# Caffeine.net
KiCad netlist of a schematic drawn in EAGLE
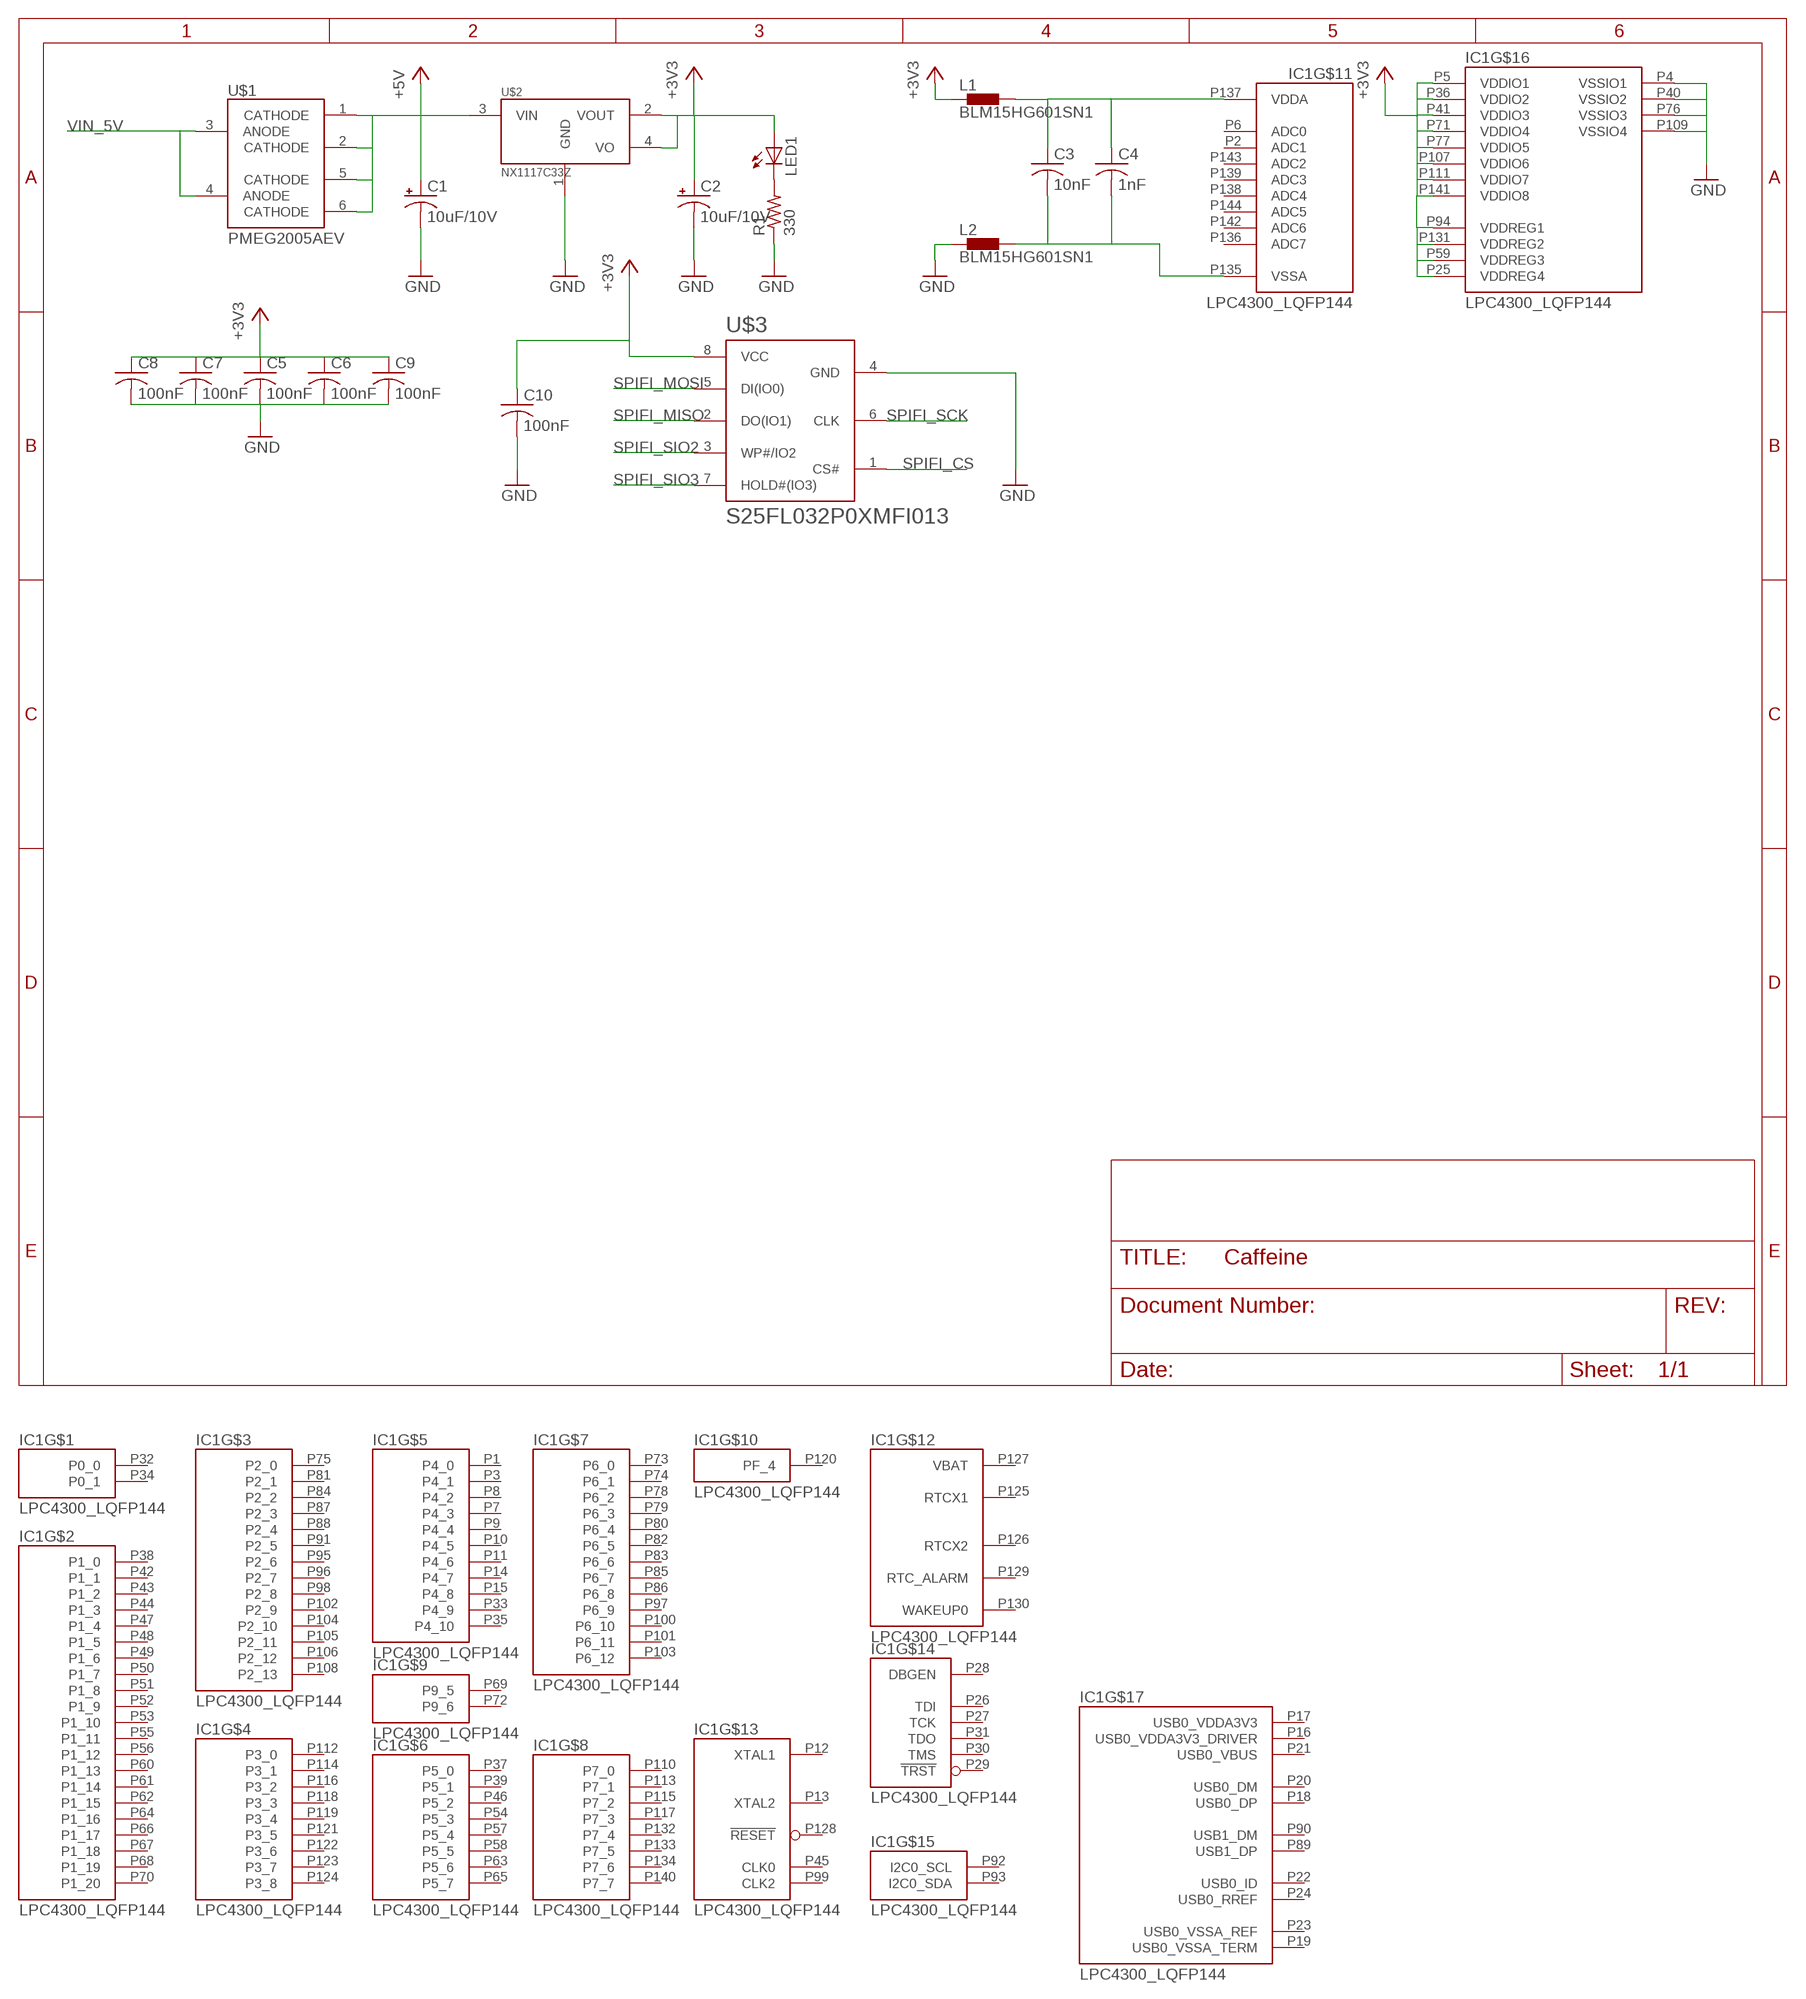
[diagram p0: schematic, sheet 1]

(export (version "E")
  (design (tool "Eeschema 10.0.6"))
  (components
    (comp (ref "C1")
      (value "10uF/10V")
      (footprint "eagle-import:CT3216")
      (libsource (lib "eagle-import") (part "CPOL-USCT3216"))
    )
    (comp (ref "C2")
      (value "10uF/10V")
      (footprint "eagle-import:CT3216")
      (libsource (lib "eagle-import") (part "CPOL-USCT3216"))
    )
    (comp (ref "C3")
      (value "10nF")
      (footprint "eagle-import:C1206")
      (libsource (lib "eagle-import") (part "C-USC1206"))
    )
    (comp (ref "C4")
      (value "1nF")
      (footprint "eagle-import:C1206")
      (libsource (lib "eagle-import") (part "C-USC1206"))
    )
    (comp (ref "C5")
      (value "100nF")
      (footprint "eagle-import:C1206")
      (libsource (lib "eagle-import") (part "C-USC1206"))
    )
    (comp (ref "C6")
      (value "100nF")
      (footprint "eagle-import:C1206")
      (libsource (lib "eagle-import") (part "C-USC1206"))
    )
    (comp (ref "C7")
      (value "100nF")
      (footprint "eagle-import:C1206")
      (libsource (lib "eagle-import") (part "C-USC1206"))
    )
    (comp (ref "C8")
      (value "100nF")
      (footprint "eagle-import:C1206")
      (libsource (lib "eagle-import") (part "C-USC1206"))
    )
    (comp (ref "C9")
      (value "100nF")
      (footprint "eagle-import:C1206")
      (libsource (lib "eagle-import") (part "C-USC1206"))
    )
    (comp (ref "C10")
      (value "100nF")
      (footprint "eagle-import:C1206")
      (libsource (lib "eagle-import") (part "C-USC1206"))
    )
    (comp (ref "IC1")
      (value "LPC4300_LQFP144")
      (footprint "eagle-import:LQFP144")
      (libsource (lib "eagle-import") (part "LPC4300_LQFP144"))
    )
    (comp (ref "L1")
      (value "BLM15HG601SN1")
      (footprint "eagle-import:0402")
      (libsource (lib "eagle-import") (part "BLM15HG601SN1"))
    )
    (comp (ref "L2")
      (value "BLM15HG601SN1")
      (footprint "eagle-import:0402")
      (libsource (lib "eagle-import") (part "BLM15HG601SN1"))
    )
    (comp (ref "LED1")
      (value "LEDCHIPLED_1206")
      (footprint "eagle-import:CHIPLED_1206")
      (libsource (lib "eagle-import") (part "LEDCHIPLED_1206"))
    )
    (comp (ref "R1")
      (value "330")
      (footprint "eagle-import:R1206")
      (libsource (lib "eagle-import") (part "R-US_R1206"))
    )
    (comp (ref "U$1")
      (value "PMEG2005AEV")
      (footprint "eagle-import:SOT666")
      (libsource (lib "eagle-import") (part "PMEG2005AEV"))
    )
    (comp (ref "U$2")
      (value "NX1117C33Z")
      (footprint "eagle-import:SOT223")
      (libsource (lib "eagle-import") (part "NX1117C33Z"))
    )
    (comp (ref "U$3")
      (value "S25FL032P0XMFI013")
      (footprint "eagle-import:SOC008")
      (libsource (lib "eagle-import") (part "S25FL032P0XMFI013"))
    )
  )
  (nets
    (net (code "1") (name "+3V3") (class "Default")
      (node (ref "C10") (pin "1") (pinfunction "1_1") (pintype "passive"))
      (node (ref "C2") (pin "+") (pinfunction "+_+") (pintype "passive"))
      (node (ref "C5") (pin "1") (pinfunction "1_1") (pintype "passive"))
      (node (ref "C6") (pin "1") (pinfunction "1_1") (pintype "passive"))
      (node (ref "C7") (pin "1") (pinfunction "1_1") (pintype "passive"))
      (node (ref "C8") (pin "1") (pinfunction "1_1") (pintype "passive"))
      (node (ref "C9") (pin "1") (pinfunction "1_1") (pintype "passive"))
      (node (ref "IC1") (pin "P107") (pinfunction "VDDIO6_P107") (pintype "power_in"))
      (node (ref "IC1") (pin "P111") (pinfunction "VDDIO7_P111") (pintype "power_in"))
      (node (ref "IC1") (pin "P131") (pinfunction "VDDREG2_P131") (pintype "power_in"))
      (node (ref "IC1") (pin "P141") (pinfunction "VDDIO8_P141") (pintype "power_in"))
      (node (ref "IC1") (pin "P25") (pinfunction "VDDREG4_P25") (pintype "power_in"))
      (node (ref "IC1") (pin "P36") (pinfunction "VDDIO2_P36") (pintype "power_in"))
      (node (ref "IC1") (pin "P41") (pinfunction "VDDIO3_P41") (pintype "power_in"))
      (node (ref "IC1") (pin "P5") (pinfunction "VDDIO1_P5") (pintype "power_in"))
      (node (ref "IC1") (pin "P59") (pinfunction "VDDREG3_P59") (pintype "power_in"))
      (node (ref "IC1") (pin "P71") (pinfunction "VDDIO4_P71") (pintype "power_in"))
      (node (ref "IC1") (pin "P77") (pinfunction "VDDIO5_P77") (pintype "power_in"))
      (node (ref "IC1") (pin "P94") (pinfunction "VDDREG1_P94") (pintype "power_in"))
      (node (ref "L1") (pin "1") (pinfunction "1_1") (pintype "passive"))
      (node (ref "LED1") (pin "A") (pinfunction "A_A") (pintype "passive"))
      (node (ref "U$2") (pin "2") (pinfunction "VOUT_2") (pintype "power_in"))
      (node (ref "U$2") (pin "4") (pinfunction "VO_4") (pintype "power_in"))
      (node (ref "U$3") (pin "8") (pinfunction "VCC_8") (pintype "power_in"))
    )
    (net (code "2") (name "+5V") (class "Default")
      (node (ref "C1") (pin "+") (pinfunction "+_+") (pintype "passive"))
      (node (ref "U$1") (pin "1") (pinfunction "CATHODE_1") (pintype "passive"))
      (node (ref "U$1") (pin "2") (pinfunction "CATHODE_2") (pintype "passive"))
      (node (ref "U$1") (pin "5") (pinfunction "CATHODE_5") (pintype "passive"))
      (node (ref "U$1") (pin "6") (pinfunction "CATHODE_6") (pintype "passive"))
      (node (ref "U$2") (pin "3") (pinfunction "VIN_3") (pintype "power_in"))
    )
    (net (code "3") (name "/SPIFI_CS") (class "Default")
      (node (ref "U$3") (pin "1") (pinfunction "CS#_1") (pintype "bidirectional"))
    )
    (net (code "4") (name "/SPIFI_MISO") (class "Default")
      (node (ref "U$3") (pin "2") (pinfunction "DO(IO1)_2") (pintype "bidirectional"))
    )
    (net (code "5") (name "/SPIFI_MOSI") (class "Default")
      (node (ref "U$3") (pin "5") (pinfunction "DI(IO0)_5") (pintype "bidirectional"))
    )
    (net (code "6") (name "/SPIFI_SCK") (class "Default")
      (node (ref "U$3") (pin "6") (pinfunction "CLK_6") (pintype "bidirectional"))
    )
    (net (code "7") (name "/SPIFI_SIO2") (class "Default")
      (node (ref "U$3") (pin "3") (pinfunction "WP#/IO2_3") (pintype "bidirectional"))
    )
    (net (code "8") (name "/SPIFI_SIO3") (class "Default")
      (node (ref "U$3") (pin "7") (pinfunction "HOLD#(IO3)_7") (pintype "bidirectional"))
    )
    (net (code "9") (name "/VBAT") (class "Default")
      (node (ref "IC1") (pin "P127") (pinfunction "VBAT_P127") (pintype "power_in"))
    )
    (net (code "10") (name "/VIN_5V") (class "Default")
      (node (ref "U$1") (pin "3") (pinfunction "ANODE_3") (pintype "passive"))
      (node (ref "U$1") (pin "4") (pinfunction "ANODE_4") (pintype "passive"))
    )
    (net (code "11") (name "GND") (class "Default")
      (node (ref "C1") (pin "-") (pinfunction "-_-") (pintype "passive"))
      (node (ref "C10") (pin "2") (pinfunction "2_2") (pintype "passive"))
      (node (ref "C2") (pin "-") (pinfunction "-_-") (pintype "passive"))
      (node (ref "C5") (pin "2") (pinfunction "2_2") (pintype "passive"))
      (node (ref "C6") (pin "2") (pinfunction "2_2") (pintype "passive"))
      (node (ref "C7") (pin "2") (pinfunction "2_2") (pintype "passive"))
      (node (ref "C8") (pin "2") (pinfunction "2_2") (pintype "passive"))
      (node (ref "C9") (pin "2") (pinfunction "2_2") (pintype "passive"))
      (node (ref "IC1") (pin "P109") (pinfunction "VSSIO4_P109") (pintype "power_in"))
      (node (ref "IC1") (pin "P4") (pinfunction "VSSIO1_P4") (pintype "power_in"))
      (node (ref "IC1") (pin "P40") (pinfunction "VSSIO2_P40") (pintype "power_in"))
      (node (ref "IC1") (pin "P76") (pinfunction "VSSIO3_P76") (pintype "power_in"))
      (node (ref "L2") (pin "1") (pinfunction "1_1") (pintype "passive"))
      (node (ref "R1") (pin "1") (pinfunction "1_1") (pintype "passive"))
      (node (ref "U$2") (pin "1") (pinfunction "GND_1") (pintype "power_in"))
      (node (ref "U$3") (pin "4") (pinfunction "GND_4") (pintype "power_in"))
    )
    (net (code "12") (name "Net-(IC1C-VDDA)") (class "Default")
      (node (ref "C3") (pin "1") (pinfunction "1_1") (pintype "passive"))
      (node (ref "C4") (pin "1") (pinfunction "1_1") (pintype "passive"))
      (node (ref "IC1") (pin "P137") (pinfunction "VDDA_P137") (pintype "power_in"))
      (node (ref "L1") (pin "2") (pinfunction "2_2") (pintype "passive"))
    )
    (net (code "13") (name "Net-(IC1C-VSSA)") (class "Default")
      (node (ref "C3") (pin "2") (pinfunction "2_2") (pintype "passive"))
      (node (ref "C4") (pin "2") (pinfunction "2_2") (pintype "passive"))
      (node (ref "IC1") (pin "P135") (pinfunction "VSSA_P135") (pintype "power_in"))
      (node (ref "L2") (pin "2") (pinfunction "2_2") (pintype "passive"))
    )
    (net (code "14") (name "Net-(LED1-PadC)") (class "Default")
      (node (ref "LED1") (pin "C") (pinfunction "C_C") (pintype "passive"))
      (node (ref "R1") (pin "2") (pinfunction "2_2") (pintype "passive"))
    )
    (net (code "15") (name "unconnected-(IC1A-P0_0-PadP32)") (class "Default")
      (node (ref "IC1") (pin "P32") (pinfunction "P0_0_P32") (pintype "bidirectional"))
    )
    (net (code "16") (name "unconnected-(IC1A-P0_1-PadP34)") (class "Default")
      (node (ref "IC1") (pin "P34") (pinfunction "P0_1_P34") (pintype "bidirectional"))
    )
    (net (code "17") (name "unconnected-(IC1B-PF_4-PadP120)") (class "Default")
      (node (ref "IC1") (pin "P120") (pinfunction "PF_4_P120") (pintype "bidirectional"))
    )
    (net (code "18") (name "unconnected-(IC1C-ADC0-PadP6)") (class "Default")
      (node (ref "IC1") (pin "P6") (pinfunction "ADC0_P6") (pintype "input"))
    )
    (net (code "19") (name "unconnected-(IC1C-ADC1-PadP2)") (class "Default")
      (node (ref "IC1") (pin "P2") (pinfunction "ADC1_P2") (pintype "input"))
    )
    (net (code "20") (name "unconnected-(IC1C-ADC2-PadP143)") (class "Default")
      (node (ref "IC1") (pin "P143") (pinfunction "ADC2_P143") (pintype "input"))
    )
    (net (code "21") (name "unconnected-(IC1C-ADC3-PadP139)") (class "Default")
      (node (ref "IC1") (pin "P139") (pinfunction "ADC3_P139") (pintype "input"))
    )
    (net (code "22") (name "unconnected-(IC1C-ADC4-PadP138)") (class "Default")
      (node (ref "IC1") (pin "P138") (pinfunction "ADC4_P138") (pintype "input"))
    )
    (net (code "23") (name "unconnected-(IC1C-ADC5-PadP144)") (class "Default")
      (node (ref "IC1") (pin "P144") (pinfunction "ADC5_P144") (pintype "input"))
    )
    (net (code "24") (name "unconnected-(IC1C-ADC6-PadP142)") (class "Default")
      (node (ref "IC1") (pin "P142") (pinfunction "ADC6_P142") (pintype "input"))
    )
    (net (code "25") (name "unconnected-(IC1C-ADC7-PadP136)") (class "Default")
      (node (ref "IC1") (pin "P136") (pinfunction "ADC7_P136") (pintype "input"))
    )
    (net (code "26") (name "unconnected-(IC1D-RTCX1-PadP125)") (class "Default")
      (node (ref "IC1") (pin "P125") (pinfunction "RTCX1_P125") (pintype "input"))
    )
    (net (code "27") (name "unconnected-(IC1D-RTCX2-PadP126)") (class "Default")
      (node (ref "IC1") (pin "P126") (pinfunction "RTCX2_P126") (pintype "output"))
    )
    (net (code "28") (name "unconnected-(IC1D-RTC_ALARM-PadP129)") (class "Default")
      (node (ref "IC1") (pin "P129") (pinfunction "RTC_ALARM_P129") (pintype "output"))
    )
    (net (code "29") (name "unconnected-(IC1D-WAKEUP0-PadP130)") (class "Default")
      (node (ref "IC1") (pin "P130") (pinfunction "WAKEUP0_P130") (pintype "input"))
    )
    (net (code "30") (name "unconnected-(IC1E-CLK0-PadP45)") (class "Default")
      (node (ref "IC1") (pin "P45") (pinfunction "CLK0_P45") (pintype "output"))
    )
    (net (code "31") (name "unconnected-(IC1E-CLK2-PadP99)") (class "Default")
      (node (ref "IC1") (pin "P99") (pinfunction "CLK2_P99") (pintype "output"))
    )
    (net (code "32") (name "unconnected-(IC1E-XTAL1-PadP12)") (class "Default")
      (node (ref "IC1") (pin "P12") (pinfunction "XTAL1_P12") (pintype "input"))
    )
    (net (code "33") (name "unconnected-(IC1E-XTAL2-PadP13)") (class "Default")
      (node (ref "IC1") (pin "P13") (pinfunction "XTAL2_P13") (pintype "output"))
    )
    (net (code "34") (name "unconnected-(IC1E-~{RESET}-PadP128)") (class "Default")
      (node (ref "IC1") (pin "P128") (pinfunction "~{RESET}_P128") (pintype "input"))
    )
    (net (code "35") (name "unconnected-(IC1F-DBGEN-PadP28)") (class "Default")
      (node (ref "IC1") (pin "P28") (pinfunction "DBGEN_P28") (pintype "input"))
    )
    (net (code "36") (name "unconnected-(IC1F-TCK-PadP27)") (class "Default")
      (node (ref "IC1") (pin "P27") (pinfunction "TCK_P27") (pintype "bidirectional"))
    )
    (net (code "37") (name "unconnected-(IC1F-TDI-PadP26)") (class "Default")
      (node (ref "IC1") (pin "P26") (pinfunction "TDI_P26") (pintype "bidirectional"))
    )
    (net (code "38") (name "unconnected-(IC1F-TDO-PadP31)") (class "Default")
      (node (ref "IC1") (pin "P31") (pinfunction "TDO_P31") (pintype "bidirectional"))
    )
    (net (code "39") (name "unconnected-(IC1F-TMS-PadP30)") (class "Default")
      (node (ref "IC1") (pin "P30") (pinfunction "TMS_P30") (pintype "bidirectional"))
    )
    (net (code "40") (name "unconnected-(IC1F-~{TRST}-PadP29)") (class "Default")
      (node (ref "IC1") (pin "P29") (pinfunction "~{TRST}_P29") (pintype "bidirectional"))
    )
    (net (code "41") (name "unconnected-(IC1G-I2C0_SCL-PadP92)") (class "Default")
      (node (ref "IC1") (pin "P92") (pinfunction "I2C0_SCL_P92") (pintype "bidirectional"))
    )
    (net (code "42") (name "unconnected-(IC1G-I2C0_SDA-PadP93)") (class "Default")
      (node (ref "IC1") (pin "P93") (pinfunction "I2C0_SDA_P93") (pintype "bidirectional"))
    )
    (net (code "43") (name "unconnected-(IC1I-USB0_DM-PadP20)") (class "Default")
      (node (ref "IC1") (pin "P20") (pinfunction "USB0_DM_P20") (pintype "bidirectional"))
    )
    (net (code "44") (name "unconnected-(IC1I-USB0_DP-PadP18)") (class "Default")
      (node (ref "IC1") (pin "P18") (pinfunction "USB0_DP_P18") (pintype "bidirectional"))
    )
    (net (code "45") (name "unconnected-(IC1I-USB0_ID-PadP22)") (class "Default")
      (node (ref "IC1") (pin "P22") (pinfunction "USB0_ID_P22") (pintype "bidirectional"))
    )
    (net (code "46") (name "unconnected-(IC1I-USB0_RREF-PadP24)") (class "Default")
      (node (ref "IC1") (pin "P24") (pinfunction "USB0_RREF_P24") (pintype "bidirectional"))
    )
    (net (code "47") (name "unconnected-(IC1I-USB0_VBUS-PadP21)") (class "Default")
      (node (ref "IC1") (pin "P21") (pinfunction "USB0_VBUS_P21") (pintype "bidirectional"))
    )
    (net (code "48") (name "unconnected-(IC1I-USB0_VDDA3V3-PadP17)") (class "Default")
      (node (ref "IC1") (pin "P17") (pinfunction "USB0_VDDA3V3_P17") (pintype "bidirectional"))
    )
    (net (code "49") (name "unconnected-(IC1I-USB0_VDDA3V3_DRIVER-PadP16)") (class "Default")
      (node (ref "IC1") (pin "P16") (pinfunction "USB0_VDDA3V3_DRIVER_P16") (pintype "bidirectional"))
    )
    (net (code "50") (name "unconnected-(IC1I-USB0_VSSA_REF-PadP23)") (class "Default")
      (node (ref "IC1") (pin "P23") (pinfunction "USB0_VSSA_REF_P23") (pintype "bidirectional"))
    )
    (net (code "51") (name "unconnected-(IC1I-USB0_VSSA_TERM-PadP19)") (class "Default")
      (node (ref "IC1") (pin "P19") (pinfunction "USB0_VSSA_TERM_P19") (pintype "bidirectional"))
    )
    (net (code "52") (name "unconnected-(IC1I-USB1_DM-PadP90)") (class "Default")
      (node (ref "IC1") (pin "P90") (pinfunction "USB1_DM_P90") (pintype "bidirectional"))
    )
    (net (code "53") (name "unconnected-(IC1I-USB1_DP-PadP89)") (class "Default")
      (node (ref "IC1") (pin "P89") (pinfunction "USB1_DP_P89") (pintype "bidirectional"))
    )
    (net (code "54") (name "unconnected-(IC1J-P1_0-PadP38)") (class "Default")
      (node (ref "IC1") (pin "P38") (pinfunction "P1_0_P38") (pintype "bidirectional"))
    )
    (net (code "55") (name "unconnected-(IC1J-P1_1-PadP42)") (class "Default")
      (node (ref "IC1") (pin "P42") (pinfunction "P1_1_P42") (pintype "bidirectional"))
    )
    (net (code "56") (name "unconnected-(IC1J-P1_2-PadP43)") (class "Default")
      (node (ref "IC1") (pin "P43") (pinfunction "P1_2_P43") (pintype "bidirectional"))
    )
    (net (code "57") (name "unconnected-(IC1J-P1_3-PadP44)") (class "Default")
      (node (ref "IC1") (pin "P44") (pinfunction "P1_3_P44") (pintype "bidirectional"))
    )
    (net (code "58") (name "unconnected-(IC1J-P1_4-PadP47)") (class "Default")
      (node (ref "IC1") (pin "P47") (pinfunction "P1_4_P47") (pintype "bidirectional"))
    )
    (net (code "59") (name "unconnected-(IC1J-P1_5-PadP48)") (class "Default")
      (node (ref "IC1") (pin "P48") (pinfunction "P1_5_P48") (pintype "bidirectional"))
    )
    (net (code "60") (name "unconnected-(IC1J-P1_6-PadP49)") (class "Default")
      (node (ref "IC1") (pin "P49") (pinfunction "P1_6_P49") (pintype "bidirectional"))
    )
    (net (code "61") (name "unconnected-(IC1J-P1_7-PadP50)") (class "Default")
      (node (ref "IC1") (pin "P50") (pinfunction "P1_7_P50") (pintype "bidirectional"))
    )
    (net (code "62") (name "unconnected-(IC1J-P1_8-PadP51)") (class "Default")
      (node (ref "IC1") (pin "P51") (pinfunction "P1_8_P51") (pintype "bidirectional"))
    )
    (net (code "63") (name "unconnected-(IC1J-P1_9-PadP52)") (class "Default")
      (node (ref "IC1") (pin "P52") (pinfunction "P1_9_P52") (pintype "bidirectional"))
    )
    (net (code "64") (name "unconnected-(IC1J-P1_10-PadP53)") (class "Default")
      (node (ref "IC1") (pin "P53") (pinfunction "P1_10_P53") (pintype "bidirectional"))
    )
    (net (code "65") (name "unconnected-(IC1J-P1_11-PadP55)") (class "Default")
      (node (ref "IC1") (pin "P55") (pinfunction "P1_11_P55") (pintype "bidirectional"))
    )
    (net (code "66") (name "unconnected-(IC1J-P1_12-PadP56)") (class "Default")
      (node (ref "IC1") (pin "P56") (pinfunction "P1_12_P56") (pintype "bidirectional"))
    )
    (net (code "67") (name "unconnected-(IC1J-P1_13-PadP60)") (class "Default")
      (node (ref "IC1") (pin "P60") (pinfunction "P1_13_P60") (pintype "bidirectional"))
    )
    (net (code "68") (name "unconnected-(IC1J-P1_14-PadP61)") (class "Default")
      (node (ref "IC1") (pin "P61") (pinfunction "P1_14_P61") (pintype "bidirectional"))
    )
    (net (code "69") (name "unconnected-(IC1J-P1_15-PadP62)") (class "Default")
      (node (ref "IC1") (pin "P62") (pinfunction "P1_15_P62") (pintype "bidirectional"))
    )
    (net (code "70") (name "unconnected-(IC1J-P1_16-PadP64)") (class "Default")
      (node (ref "IC1") (pin "P64") (pinfunction "P1_16_P64") (pintype "bidirectional"))
    )
    (net (code "71") (name "unconnected-(IC1J-P1_17-PadP66)") (class "Default")
      (node (ref "IC1") (pin "P66") (pinfunction "P1_17_P66") (pintype "bidirectional"))
    )
    (net (code "72") (name "unconnected-(IC1J-P1_18-PadP67)") (class "Default")
      (node (ref "IC1") (pin "P67") (pinfunction "P1_18_P67") (pintype "bidirectional"))
    )
    (net (code "73") (name "unconnected-(IC1J-P1_19-PadP68)") (class "Default")
      (node (ref "IC1") (pin "P68") (pinfunction "P1_19_P68") (pintype "bidirectional"))
    )
    (net (code "74") (name "unconnected-(IC1J-P1_20-PadP70)") (class "Default")
      (node (ref "IC1") (pin "P70") (pinfunction "P1_20_P70") (pintype "bidirectional"))
    )
    (net (code "75") (name "unconnected-(IC1K-P2_0-PadP75)") (class "Default")
      (node (ref "IC1") (pin "P75") (pinfunction "P2_0_P75") (pintype "bidirectional"))
    )
    (net (code "76") (name "unconnected-(IC1K-P2_1-PadP81)") (class "Default")
      (node (ref "IC1") (pin "P81") (pinfunction "P2_1_P81") (pintype "bidirectional"))
    )
    (net (code "77") (name "unconnected-(IC1K-P2_2-PadP84)") (class "Default")
      (node (ref "IC1") (pin "P84") (pinfunction "P2_2_P84") (pintype "bidirectional"))
    )
    (net (code "78") (name "unconnected-(IC1K-P2_3-PadP87)") (class "Default")
      (node (ref "IC1") (pin "P87") (pinfunction "P2_3_P87") (pintype "bidirectional"))
    )
    (net (code "79") (name "unconnected-(IC1K-P2_4-PadP88)") (class "Default")
      (node (ref "IC1") (pin "P88") (pinfunction "P2_4_P88") (pintype "bidirectional"))
    )
    (net (code "80") (name "unconnected-(IC1K-P2_5-PadP91)") (class "Default")
      (node (ref "IC1") (pin "P91") (pinfunction "P2_5_P91") (pintype "bidirectional"))
    )
    (net (code "81") (name "unconnected-(IC1K-P2_6-PadP95)") (class "Default")
      (node (ref "IC1") (pin "P95") (pinfunction "P2_6_P95") (pintype "bidirectional"))
    )
    (net (code "82") (name "unconnected-(IC1K-P2_7-PadP96)") (class "Default")
      (node (ref "IC1") (pin "P96") (pinfunction "P2_7_P96") (pintype "bidirectional"))
    )
    (net (code "83") (name "unconnected-(IC1K-P2_8-PadP98)") (class "Default")
      (node (ref "IC1") (pin "P98") (pinfunction "P2_8_P98") (pintype "bidirectional"))
    )
    (net (code "84") (name "unconnected-(IC1K-P2_9-PadP102)") (class "Default")
      (node (ref "IC1") (pin "P102") (pinfunction "P2_9_P102") (pintype "bidirectional"))
    )
    (net (code "85") (name "unconnected-(IC1K-P2_10-PadP104)") (class "Default")
      (node (ref "IC1") (pin "P104") (pinfunction "P2_10_P104") (pintype "bidirectional"))
    )
    (net (code "86") (name "unconnected-(IC1K-P2_11-PadP105)") (class "Default")
      (node (ref "IC1") (pin "P105") (pinfunction "P2_11_P105") (pintype "bidirectional"))
    )
    (net (code "87") (name "unconnected-(IC1K-P2_12-PadP106)") (class "Default")
      (node (ref "IC1") (pin "P106") (pinfunction "P2_12_P106") (pintype "bidirectional"))
    )
    (net (code "88") (name "unconnected-(IC1K-P2_13-PadP108)") (class "Default")
      (node (ref "IC1") (pin "P108") (pinfunction "P2_13_P108") (pintype "bidirectional"))
    )
    (net (code "89") (name "unconnected-(IC1L-P3_0-PadP112)") (class "Default")
      (node (ref "IC1") (pin "P112") (pinfunction "P3_0_P112") (pintype "bidirectional"))
    )
    (net (code "90") (name "unconnected-(IC1L-P3_1-PadP114)") (class "Default")
      (node (ref "IC1") (pin "P114") (pinfunction "P3_1_P114") (pintype "bidirectional"))
    )
    (net (code "91") (name "unconnected-(IC1L-P3_2-PadP116)") (class "Default")
      (node (ref "IC1") (pin "P116") (pinfunction "P3_2_P116") (pintype "bidirectional"))
    )
    (net (code "92") (name "unconnected-(IC1L-P3_3-PadP118)") (class "Default")
      (node (ref "IC1") (pin "P118") (pinfunction "P3_3_P118") (pintype "bidirectional"))
    )
    (net (code "93") (name "unconnected-(IC1L-P3_4-PadP119)") (class "Default")
      (node (ref "IC1") (pin "P119") (pinfunction "P3_4_P119") (pintype "bidirectional"))
    )
    (net (code "94") (name "unconnected-(IC1L-P3_5-PadP121)") (class "Default")
      (node (ref "IC1") (pin "P121") (pinfunction "P3_5_P121") (pintype "bidirectional"))
    )
    (net (code "95") (name "unconnected-(IC1L-P3_6-PadP122)") (class "Default")
      (node (ref "IC1") (pin "P122") (pinfunction "P3_6_P122") (pintype "bidirectional"))
    )
    (net (code "96") (name "unconnected-(IC1L-P3_7-PadP123)") (class "Default")
      (node (ref "IC1") (pin "P123") (pinfunction "P3_7_P123") (pintype "bidirectional"))
    )
    (net (code "97") (name "unconnected-(IC1L-P3_8-PadP124)") (class "Default")
      (node (ref "IC1") (pin "P124") (pinfunction "P3_8_P124") (pintype "bidirectional"))
    )
    (net (code "98") (name "unconnected-(IC1M-P4_0-PadP1)") (class "Default")
      (node (ref "IC1") (pin "P1") (pinfunction "P4_0_P1") (pintype "bidirectional"))
    )
    (net (code "99") (name "unconnected-(IC1M-P4_1-PadP3)") (class "Default")
      (node (ref "IC1") (pin "P3") (pinfunction "P4_1_P3") (pintype "bidirectional"))
    )
    (net (code "100") (name "unconnected-(IC1M-P4_2-PadP8)") (class "Default")
      (node (ref "IC1") (pin "P8") (pinfunction "P4_2_P8") (pintype "bidirectional"))
    )
    (net (code "101") (name "unconnected-(IC1M-P4_3-PadP7)") (class "Default")
      (node (ref "IC1") (pin "P7") (pinfunction "P4_3_P7") (pintype "bidirectional"))
    )
    (net (code "102") (name "unconnected-(IC1M-P4_4-PadP9)") (class "Default")
      (node (ref "IC1") (pin "P9") (pinfunction "P4_4_P9") (pintype "bidirectional"))
    )
    (net (code "103") (name "unconnected-(IC1M-P4_5-PadP10)") (class "Default")
      (node (ref "IC1") (pin "P10") (pinfunction "P4_5_P10") (pintype "bidirectional"))
    )
    (net (code "104") (name "unconnected-(IC1M-P4_6-PadP11)") (class "Default")
      (node (ref "IC1") (pin "P11") (pinfunction "P4_6_P11") (pintype "bidirectional"))
    )
    (net (code "105") (name "unconnected-(IC1M-P4_7-PadP14)") (class "Default")
      (node (ref "IC1") (pin "P14") (pinfunction "P4_7_P14") (pintype "bidirectional"))
    )
    (net (code "106") (name "unconnected-(IC1M-P4_8-PadP15)") (class "Default")
      (node (ref "IC1") (pin "P15") (pinfunction "P4_8_P15") (pintype "bidirectional"))
    )
    (net (code "107") (name "unconnected-(IC1M-P4_9-PadP33)") (class "Default")
      (node (ref "IC1") (pin "P33") (pinfunction "P4_9_P33") (pintype "bidirectional"))
    )
    (net (code "108") (name "unconnected-(IC1M-P4_10-PadP35)") (class "Default")
      (node (ref "IC1") (pin "P35") (pinfunction "P4_10_P35") (pintype "bidirectional"))
    )
    (net (code "109") (name "unconnected-(IC1N-P5_0-PadP37)") (class "Default")
      (node (ref "IC1") (pin "P37") (pinfunction "P5_0_P37") (pintype "bidirectional"))
    )
    (net (code "110") (name "unconnected-(IC1N-P5_1-PadP39)") (class "Default")
      (node (ref "IC1") (pin "P39") (pinfunction "P5_1_P39") (pintype "bidirectional"))
    )
    (net (code "111") (name "unconnected-(IC1N-P5_2-PadP46)") (class "Default")
      (node (ref "IC1") (pin "P46") (pinfunction "P5_2_P46") (pintype "bidirectional"))
    )
    (net (code "112") (name "unconnected-(IC1N-P5_3-PadP54)") (class "Default")
      (node (ref "IC1") (pin "P54") (pinfunction "P5_3_P54") (pintype "bidirectional"))
    )
    (net (code "113") (name "unconnected-(IC1N-P5_4-PadP57)") (class "Default")
      (node (ref "IC1") (pin "P57") (pinfunction "P5_4_P57") (pintype "bidirectional"))
    )
    (net (code "114") (name "unconnected-(IC1N-P5_5-PadP58)") (class "Default")
      (node (ref "IC1") (pin "P58") (pinfunction "P5_5_P58") (pintype "bidirectional"))
    )
    (net (code "115") (name "unconnected-(IC1N-P5_6-PadP63)") (class "Default")
      (node (ref "IC1") (pin "P63") (pinfunction "P5_6_P63") (pintype "bidirectional"))
    )
    (net (code "116") (name "unconnected-(IC1N-P5_7-PadP65)") (class "Default")
      (node (ref "IC1") (pin "P65") (pinfunction "P5_7_P65") (pintype "bidirectional"))
    )
    (net (code "117") (name "unconnected-(IC1O-P6_0-PadP73)") (class "Default")
      (node (ref "IC1") (pin "P73") (pinfunction "P6_0_P73") (pintype "bidirectional"))
    )
    (net (code "118") (name "unconnected-(IC1O-P6_1-PadP74)") (class "Default")
      (node (ref "IC1") (pin "P74") (pinfunction "P6_1_P74") (pintype "bidirectional"))
    )
    (net (code "119") (name "unconnected-(IC1O-P6_2-PadP78)") (class "Default")
      (node (ref "IC1") (pin "P78") (pinfunction "P6_2_P78") (pintype "bidirectional"))
    )
    (net (code "120") (name "unconnected-(IC1O-P6_3-PadP79)") (class "Default")
      (node (ref "IC1") (pin "P79") (pinfunction "P6_3_P79") (pintype "bidirectional"))
    )
    (net (code "121") (name "unconnected-(IC1O-P6_4-PadP80)") (class "Default")
      (node (ref "IC1") (pin "P80") (pinfunction "P6_4_P80") (pintype "bidirectional"))
    )
    (net (code "122") (name "unconnected-(IC1O-P6_5-PadP82)") (class "Default")
      (node (ref "IC1") (pin "P82") (pinfunction "P6_5_P82") (pintype "bidirectional"))
    )
    (net (code "123") (name "unconnected-(IC1O-P6_6-PadP83)") (class "Default")
      (node (ref "IC1") (pin "P83") (pinfunction "P6_6_P83") (pintype "bidirectional"))
    )
    (net (code "124") (name "unconnected-(IC1O-P6_7-PadP85)") (class "Default")
      (node (ref "IC1") (pin "P85") (pinfunction "P6_7_P85") (pintype "bidirectional"))
    )
    (net (code "125") (name "unconnected-(IC1O-P6_8-PadP86)") (class "Default")
      (node (ref "IC1") (pin "P86") (pinfunction "P6_8_P86") (pintype "bidirectional"))
    )
    (net (code "126") (name "unconnected-(IC1O-P6_9-PadP97)") (class "Default")
      (node (ref "IC1") (pin "P97") (pinfunction "P6_9_P97") (pintype "bidirectional"))
    )
    (net (code "127") (name "unconnected-(IC1O-P6_10-PadP100)") (class "Default")
      (node (ref "IC1") (pin "P100") (pinfunction "P6_10_P100") (pintype "bidirectional"))
    )
    (net (code "128") (name "unconnected-(IC1O-P6_11-PadP101)") (class "Default")
      (node (ref "IC1") (pin "P101") (pinfunction "P6_11_P101") (pintype "bidirectional"))
    )
    (net (code "129") (name "unconnected-(IC1O-P6_12-PadP103)") (class "Default")
      (node (ref "IC1") (pin "P103") (pinfunction "P6_12_P103") (pintype "bidirectional"))
    )
    (net (code "130") (name "unconnected-(IC1P-P7_0-PadP110)") (class "Default")
      (node (ref "IC1") (pin "P110") (pinfunction "P7_0_P110") (pintype "bidirectional"))
    )
    (net (code "131") (name "unconnected-(IC1P-P7_1-PadP113)") (class "Default")
      (node (ref "IC1") (pin "P113") (pinfunction "P7_1_P113") (pintype "bidirectional"))
    )
    (net (code "132") (name "unconnected-(IC1P-P7_2-PadP115)") (class "Default")
      (node (ref "IC1") (pin "P115") (pinfunction "P7_2_P115") (pintype "bidirectional"))
    )
    (net (code "133") (name "unconnected-(IC1P-P7_3-PadP117)") (class "Default")
      (node (ref "IC1") (pin "P117") (pinfunction "P7_3_P117") (pintype "bidirectional"))
    )
    (net (code "134") (name "unconnected-(IC1P-P7_4-PadP132)") (class "Default")
      (node (ref "IC1") (pin "P132") (pinfunction "P7_4_P132") (pintype "bidirectional"))
    )
    (net (code "135") (name "unconnected-(IC1P-P7_5-PadP133)") (class "Default")
      (node (ref "IC1") (pin "P133") (pinfunction "P7_5_P133") (pintype "bidirectional"))
    )
    (net (code "136") (name "unconnected-(IC1P-P7_6-PadP134)") (class "Default")
      (node (ref "IC1") (pin "P134") (pinfunction "P7_6_P134") (pintype "bidirectional"))
    )
    (net (code "137") (name "unconnected-(IC1P-P7_7-PadP140)") (class "Default")
      (node (ref "IC1") (pin "P140") (pinfunction "P7_7_P140") (pintype "bidirectional"))
    )
    (net (code "138") (name "unconnected-(IC1Q-P9_5-PadP69)") (class "Default")
      (node (ref "IC1") (pin "P69") (pinfunction "P9_5_P69") (pintype "bidirectional"))
    )
    (net (code "139") (name "unconnected-(IC1Q-P9_6-PadP72)") (class "Default")
      (node (ref "IC1") (pin "P72") (pinfunction "P9_6_P72") (pintype "bidirectional"))
    )
  )
)
